# SPL1301_for_Cal_V1_0.net
KiCad netlist of a schematic drawn in Altium Designer
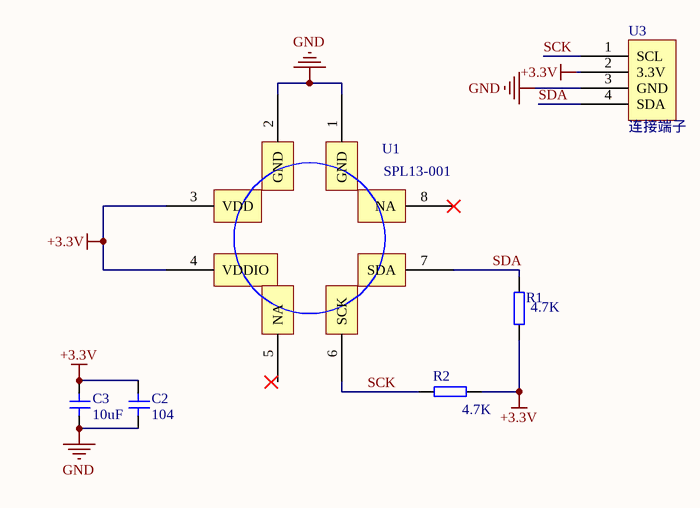
[diagram p0: SPL1301 for Cal V1.0.SchDoc]

(export (version "E")
  (design (tool "Eeschema 10.0.6"))
  (components
    (comp (ref "C2")
      (value "104")
      (footprint "0603C")
      (description "无极贴片电容")
      (libsource (lib "集大电协1.5(1)") (part "Cap1"))
    )
    (comp (ref "C3")
      (value "10uF")
      (footprint "0603C")
      (description "无极贴片电容")
      (libsource (lib "集大电协1.5(1)") (part "Cap1"))
    )
    (comp (ref "R1")
      (value "4.7K")
      (footprint "0603R")
      (description "电阻")
      (libsource (lib "My ku") (part "Res"))
    )
    (comp (ref "R2")
      (value "4.7K")
      (footprint "0603R")
      (description "电阻")
      (libsource (lib "My ku") (part "Res"))
    )
    (comp (ref "U1")
      (value "SPL13-001")
      (footprint "SPL13-001")
      (libsource (lib "Schlib1") (part "SPL13-001_1"))
    )
    (comp (ref "U3") (value "连接端子") (footprint "连接端子") (libsource (lib "集大电协1.1.5") (part "连接端子")))
  )
  (nets
    (net (code "1") (name "+3.3V") (class "Default")
      (node (ref "C2") (pin "2") (pinfunction "2_2") (pintype "passive"))
      (node (ref "C3") (pin "2") (pinfunction "2_2") (pintype "passive"))
      (node (ref "R1") (pin "1") (pinfunction "1_1") (pintype "passive"))
      (node (ref "R2") (pin "1") (pinfunction "1_1") (pintype "passive"))
      (node (ref "U1") (pin "3") (pinfunction "VDD_3") (pintype "passive"))
      (node (ref "U1") (pin "4") (pinfunction "VDDIO_4") (pintype "passive"))
      (node (ref "U3") (pin "2") (pinfunction "3.3V_2") (pintype "passive"))
    )
    (net (code "2") (name "/SCK") (class "Default")
      (node (ref "R2") (pin "2") (pinfunction "2_2") (pintype "passive"))
      (node (ref "U1") (pin "6") (pinfunction "SCK_6") (pintype "passive"))
      (node (ref "U3") (pin "1") (pinfunction "SCL_1") (pintype "passive"))
    )
    (net (code "3") (name "/SDA") (class "Default")
      (node (ref "R1") (pin "2") (pinfunction "2_2") (pintype "passive"))
      (node (ref "U1") (pin "7") (pinfunction "SDA_7") (pintype "passive"))
      (node (ref "U3") (pin "4") (pinfunction "SDA_4") (pintype "passive"))
    )
    (net (code "4") (name "GND") (class "Default")
      (node (ref "C2") (pin "1") (pinfunction "1_1") (pintype "passive"))
      (node (ref "C3") (pin "1") (pinfunction "1_1") (pintype "passive"))
      (node (ref "U1") (pin "1") (pinfunction "GND_1") (pintype "passive"))
      (node (ref "U1") (pin "2") (pinfunction "GND_2") (pintype "passive"))
      (node (ref "U3") (pin "3") (pinfunction "GND_3") (pintype "passive"))
    )
    (net (code "5") (name "unconnected-(U1-NA-Pad5)") (class "Default")
      (node (ref "U1") (pin "5") (pinfunction "NA_5") (pintype "passive"))
    )
    (net (code "6") (name "unconnected-(U1-NA-Pad8)") (class "Default")
      (node (ref "U1") (pin "8") (pinfunction "NA_8") (pintype "passive+no_connect"))
    )
  )
)
